# SAMV71_Xplained_Ultra_Power_Converter.net
KiCad netlist of a schematic drawn in Altium Designer
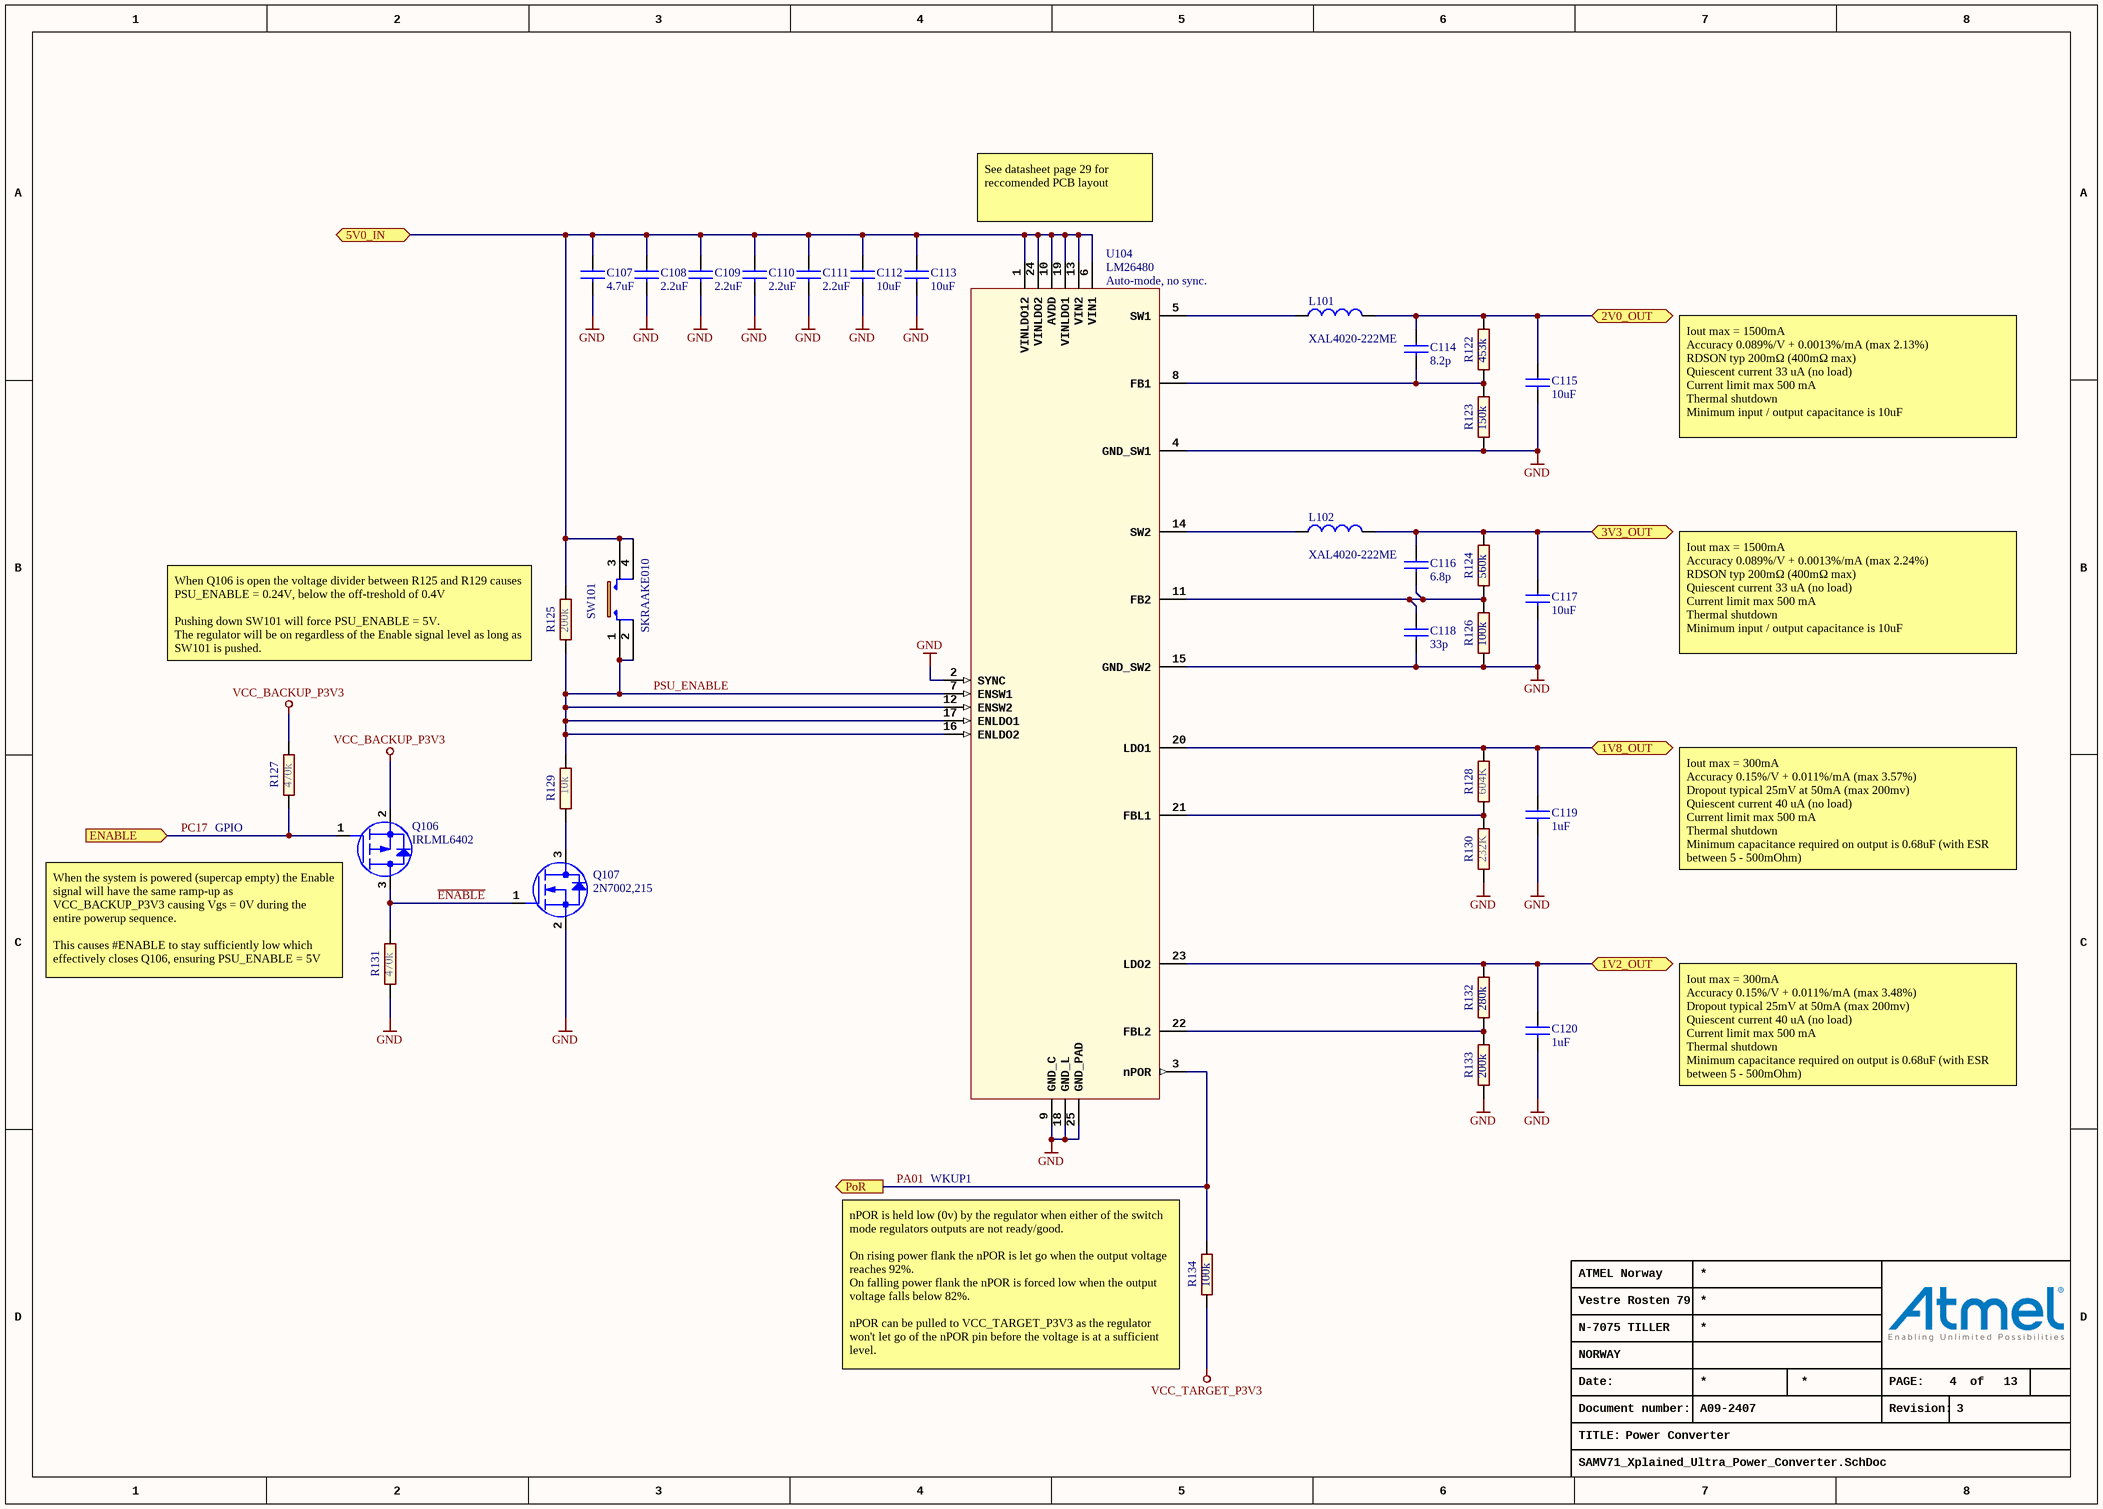
[diagram p0: SAMV71_Xplained_Ultra_Power_Converter.SchDoc]

(export (version "E")
  (design (tool "Eeschema 10.0.6"))
  (components
    (comp (ref "C107")
      (value "4.7uF")
      (footprint "AP1-00039")
      (description "Ceramic capacitor, SMD 0603, X5R, 10V, 10% (de31036)")
      (fields (field (name "TOLERANCE") "10%") (field (name "MANUFACTURER") "tdk"))
      (libsource (lib "AltiumDbLib") (part "CAP-NONPOL"))
    )
    (comp (ref "C108")
      (value "2.2uF")
      (footprint "AP1-00053")
      (description "Ceramic capacitor, SMD 0402, X5R, 6.3V, +/-20%")
      (fields (field (name "TOLERANCE") "Â±20%") (field (name "MANUFACTURER") "Kemet"))
      (libsource (lib "AltiumDbLib") (part "CAP-NONPOL"))
    )
    (comp (ref "C109")
      (value "2.2uF")
      (footprint "AP1-00053")
      (description "Ceramic capacitor, SMD 0402, X5R, 6.3V, +/-20%")
      (fields (field (name "TOLERANCE") "Â±20%") (field (name "MANUFACTURER") "Kemet"))
      (libsource (lib "AltiumDbLib") (part "CAP-NONPOL"))
    )
    (comp (ref "C110")
      (value "2.2uF")
      (footprint "AP1-00053")
      (description "Ceramic capacitor, SMD 0402, X5R, 6.3V, +/-20%")
      (fields (field (name "TOLERANCE") "Â±20%") (field (name "MANUFACTURER") "Kemet"))
      (libsource (lib "AltiumDbLib") (part "CAP-NONPOL"))
    )
    (comp (ref "C111")
      (value "2.2uF")
      (footprint "AP1-00053")
      (description "Ceramic capacitor, SMD 0402, X5R, 6.3V, +/-20%")
      (fields (field (name "TOLERANCE") "Â±20%") (field (name "MANUFACTURER") "Kemet"))
      (libsource (lib "AltiumDbLib") (part "CAP-NONPOL"))
    )
    (comp (ref "C112")
      (value "10uF")
      (footprint "AP1-00041")
      (description "Ceramic capacitor, SMD 0805, X5R, 10V, 10 %, (de19441)")
      (fields (field (name "TOLERANCE") "10%") (field (name "MANUFACTURER") "Murata"))
      (libsource (lib "AltiumDbLib") (part "CAP-NONPOL"))
    )
    (comp (ref "C113")
      (value "10uF")
      (footprint "AP1-00041")
      (description "Ceramic capacitor, SMD 0805, X5R, 10V, 10 %, (de19441)")
      (fields (field (name "TOLERANCE") "10%") (field (name "MANUFACTURER") "Murata"))
      (libsource (lib "AltiumDbLib") (part "CAP-NONPOL"))
    )
    (comp (ref "C114")
      (value "8.2p")
      (footprint "AP1-00053")
      (description "Ceramic capacitor, SMD 0402, NP0, 50V, +/-5%")
      (fields (field (name "TOLERANCE") "50V, +/-5%"))
      (libsource (lib "AltiumDbLib") (part "CAP-NONPOL"))
    )
    (comp (ref "C115")
      (value "10uF")
      (footprint "AP1-00041")
      (description "Ceramic capacitor, SMD 0805, X5R, 10V, 10 %, (de19441)")
      (fields (field (name "TOLERANCE") "10%") (field (name "MANUFACTURER") "Murata"))
      (libsource (lib "AltiumDbLib") (part "CAP-NONPOL"))
    )
    (comp (ref "C116")
      (value "6.8p")
      (footprint "AP1-00053")
      (description "Ceramic capacitor, SMD 0402, NP0, 50V, +/-5%")
      (fields (field (name "TOLERANCE") "50V, +/-5%"))
      (libsource (lib "AltiumDbLib") (part "CAP-NONPOL"))
    )
    (comp (ref "C117")
      (value "10uF")
      (footprint "AP1-00041")
      (description "Ceramic capacitor, SMD 0805, X5R, 10V, 10 %, (de19441)")
      (fields (field (name "TOLERANCE") "10%") (field (name "MANUFACTURER") "Murata"))
      (libsource (lib "AltiumDbLib") (part "CAP-NONPOL"))
    )
    (comp (ref "C118")
      (value "33p")
      (footprint "AP1-00053")
      (description "Ceramic capacitor, SMD 0402, NP0, 50V, +/-5%")
      (fields (field (name "TOLERANCE") "50V, +/-5%"))
      (libsource (lib "AltiumDbLib") (part "CAP-NONPOL"))
    )
    (comp (ref "C119")
      (value "1uF")
      (footprint "AP1-00053")
      (description "Ceramic capacitor, SMD 0402, X5R, 10V, ±10 %")
      (fields (field (name "MANUFACTURER") "AVX") (field (name "MPN") "0402ZD105KAT2A"))
      (libsource (lib "AltiumDbLib") (part "CAP-NONPOL"))
    )
    (comp (ref "C120")
      (value "1uF")
      (footprint "AP1-00053")
      (description "Ceramic capacitor, SMD 0402, X5R, 10V, ±10 %")
      (fields (field (name "MANUFACTURER") "AVX") (field (name "MPN") "0402ZD105KAT2A"))
      (libsource (lib "AltiumDbLib") (part "CAP-NONPOL"))
    )
    (comp (ref "L101")
      (value "XAL4020-222ME")
      (footprint "AP3-00119")
      (description "2.2ÂµH Shielded Power Inductor, 4x4x2mm, Isat=5.6A , Irms=4.0A , DCR=35.2mÎ©")
      (fields (field (name "TOLERANCE") "20%") (field (name "MANUFACTURER") "Coilcraft"))
      (libsource (lib "AltiumDbLib") (part "INDUCTOR"))
    )
    (comp (ref "L102")
      (value "XAL4020-222ME")
      (footprint "AP3-00119")
      (description "2.2ÂµH Shielded Power Inductor, 4x4x2mm, Isat=5.6A , Irms=4.0A , DCR=35.2mÎ©")
      (fields (field (name "TOLERANCE") "20%") (field (name "MANUFACTURER") "Coilcraft"))
      (libsource (lib "AltiumDbLib") (part "INDUCTOR"))
    )
    (comp (ref "Q106")
      (value "IRLML6402")
      (footprint "AP5-00002")
      (description "P-ch. MOSFET. -30V, -3.7A continuous,RDS(ON)=0.05Ohm@VGS=-4,5V, RDS(ON)=0.08Ohm@VGS=-2.5V")
      (fields (field (name "MANUFACTURER") "International Rectifier") (field (name "MPN") "IRLML6402PBF"))
      (libsource (lib "AltiumDbLib") (part "MOSFET_P_GSD"))
    )
    (comp (ref "Q107")
      (value "2N7002,215")
      (footprint "AP5-00002")
      (description "N-Channel MOSFET. 60V, 0.300A continuous, 1.2A Peak. RDS(ON) = 3.8Ohm@VGS=4.5V, VGS(th)<2.5V")
      (fields (field (name "MANUFACTURER") "NXP"))
      (libsource (lib "AltiumDbLib") (part "MOSFET_N_GSD"))
    )
    (comp (ref "R122")
      (value "453k")
      (footprint "AP2-00011")
      (description "Thick film resistor, SMD 0402, 1/16W, 1%")
      (fields (field (name "TOLERANCE") "1 %"))
      (libsource (lib "AltiumDbLib") (part "R2"))
    )
    (comp (ref "R123")
      (value "150k")
      (footprint "AP2-00011")
      (description "Thick film resistor, SMD 0402, 1/16W, 1%")
      (fields (field (name "TOLERANCE") "1 %"))
      (libsource (lib "AltiumDbLib") (part "R2"))
    )
    (comp (ref "R124")
      (value "560k")
      (footprint "AP2-00011")
      (description "Thick film resistor, SMD 0402, 1/16W, 1%")
      (fields (field (name "TOLERANCE") "1 %"))
      (libsource (lib "AltiumDbLib") (part "R2"))
    )
    (comp (ref "R125")
      (value "200k")
      (footprint "AP2-00011")
      (description "Thick film resistor, SMD 0402, 1/16W, 1%")
      (fields (field (name "TOLERANCE") "1 %"))
      (libsource (lib "AltiumDbLib") (part "R2"))
    )
    (comp (ref "R126")
      (value "100k")
      (footprint "AP2-00011")
      (description "Thick film resistor, SMD 0402, 1/16W, 1%")
      (fields (field (name "TOLERANCE") "1 %"))
      (libsource (lib "") (part "R2_1"))
    )
    (comp (ref "R127")
      (value "470k")
      (footprint "AP2-00011")
      (description "Thick film resistor, SMD 0402, 1/16W, 1%")
      (fields (field (name "TOLERANCE") "1 %"))
      (libsource (lib "AltiumDbLib") (part "R2"))
    )
    (comp (ref "R128")
      (value "604K")
      (footprint "AP2-00011")
      (description "Thick film resistor, SMD 0402, 1/16W, 1%")
      (fields (field (name "TOLERANCE") "1 %"))
      (libsource (lib "AltiumDbLib") (part "R2"))
    )
    (comp (ref "R129")
      (value "10k")
      (footprint "AP2-00011")
      (description "Thick film resistor, SMD 0402, 1/16W, 1%")
      (fields (field (name "TOLERANCE") "1 %") (field (name "MANUFACTURER") "vishay"))
      (libsource (lib "AltiumDbLib") (part "R2"))
    )
    (comp (ref "R130")
      (value "232K")
      (footprint "AP2-00011")
      (description "Thick film resistor, SMD 0402, 1/16W, 1%")
      (fields (field (name "TOLERANCE") "1 %"))
      (libsource (lib "AltiumDbLib") (part "R2"))
    )
    (comp (ref "R131")
      (value "470k")
      (footprint "AP2-00011")
      (description "Thick film resistor, SMD 0402, 1/16W, 1%")
      (fields (field (name "TOLERANCE") "1 %"))
      (libsource (lib "AltiumDbLib") (part "R2"))
    )
    (comp (ref "R132")
      (value "280k")
      (footprint "AP2-00011")
      (description "Thick film resistor, SMD 0402, 1/16W, 1%")
      (fields (field (name "TOLERANCE") "1 %"))
      (libsource (lib "AltiumDbLib") (part "R2"))
    )
    (comp (ref "R133")
      (value "200k")
      (footprint "AP2-00011")
      (description "Thick film resistor, SMD 0402, 1/16W, 1%")
      (fields (field (name "TOLERANCE") "1 %"))
      (libsource (lib "AltiumDbLib") (part "R2"))
    )
    (comp (ref "R134")
      (value "100k")
      (footprint "AP2-00011")
      (description "Thick film resistor, SMD 0402, 1/16W, 1%")
      (fields (field (name "TOLERANCE") "1 %"))
      (libsource (lib "") (part "R2_1"))
    )
    (comp (ref "SW101")
      (value "SKRAAKE010")
      (footprint "AP8-00137")
      (description "6.2x6.2 mm SMD tact switch, same as A08-0091 but less force is needed")
      (fields
        (field (name "MANUFACTURER") "ALPS")
        (field (name "Comment") "Can be ordered in low volumes from Mouser")
      )
      (libsource (lib "AltiumDbLib") (part "PUSHBUTTON1"))
    )
    (comp (ref "U104")
      (value "Auto-mode, no sync.")
      (footprint "AP6-00380")
      (description "Externally Programmable Dual High-Current Step-Down DC/DC and Dual Linear Regulators")
      (fields
        (field (name "ALTIUM_VALUE") "LM26480")
        (field (name "MANUFACTURER") "Texas Instruments")
        (field (name "MPN") "LM26480SQ-AA/NOPB")
      )
      (libsource (lib "AltiumDbLib") (part "LM26480"))
    )
  )
  (nets
    (net (code "1") (name "/1V2_OUT") (class "Default")
      (node (ref "C120") (pin "1") (pinfunction "1_1") (pintype "passive"))
      (node (ref "R132") (pin "2") (pinfunction "2_2") (pintype "passive"))
      (node (ref "U104") (pin "23") (pinfunction "LDO2_23") (pintype "power_in"))
    )
    (net (code "2") (name "/1V8_OUT") (class "Default")
      (node (ref "C119") (pin "1") (pinfunction "1_1") (pintype "passive"))
      (node (ref "R128") (pin "2") (pinfunction "2_2") (pintype "passive"))
      (node (ref "U104") (pin "20") (pinfunction "LDO1_20") (pintype "power_in"))
    )
    (net (code "3") (name "/2V0_OUT") (class "Default")
      (node (ref "C114") (pin "1") (pinfunction "1_1") (pintype "passive"))
      (node (ref "C115") (pin "1") (pinfunction "1_1") (pintype "passive"))
      (node (ref "L101") (pin "2") (pinfunction "2_2") (pintype "passive"))
      (node (ref "R122") (pin "2") (pinfunction "2_2") (pintype "passive"))
    )
    (net (code "4") (name "/3V3_OUT") (class "Default")
      (node (ref "C116") (pin "1") (pinfunction "1_1") (pintype "passive"))
      (node (ref "C117") (pin "1") (pinfunction "1_1") (pintype "passive"))
      (node (ref "L102") (pin "2") (pinfunction "2_2") (pintype "passive"))
      (node (ref "R124") (pin "2") (pinfunction "2_2") (pintype "passive"))
    )
    (net (code "5") (name "/5V0_IN") (class "Default")
      (node (ref "C107") (pin "1") (pinfunction "1_1") (pintype "passive"))
      (node (ref "C108") (pin "1") (pinfunction "1_1") (pintype "passive"))
      (node (ref "C109") (pin "1") (pinfunction "1_1") (pintype "passive"))
      (node (ref "C110") (pin "1") (pinfunction "1_1") (pintype "passive"))
      (node (ref "C111") (pin "1") (pinfunction "1_1") (pintype "passive"))
      (node (ref "C112") (pin "1") (pinfunction "1_1") (pintype "passive"))
      (node (ref "C113") (pin "1") (pinfunction "1_1") (pintype "passive"))
      (node (ref "R125") (pin "2") (pinfunction "2_2") (pintype "passive"))
      (node (ref "SW101") (pin "3") (pinfunction "3_3") (pintype "passive"))
      (node (ref "SW101") (pin "4") (pinfunction "4_4") (pintype "passive"))
      (node (ref "U104") (pin "1") (pinfunction "VINLDO12_1") (pintype "power_in"))
      (node (ref "U104") (pin "10") (pinfunction "AVDD_10") (pintype "power_in"))
      (node (ref "U104") (pin "13") (pinfunction "VIN2_13") (pintype "power_in"))
      (node (ref "U104") (pin "19") (pinfunction "VINLDO1_19") (pintype "power_in"))
      (node (ref "U104") (pin "24") (pinfunction "VINLDO2_24") (pintype "power_in"))
      (node (ref "U104") (pin "6") (pinfunction "VIN1_6") (pintype "power_in"))
    )
    (net (code "6") (name "/PA01") (class "Default")
      (node (ref "R134") (pin "1") (pinfunction "1_1") (pintype "passive"))
      (node (ref "U104") (pin "3") (pinfunction "nPOR_3") (pintype "output"))
    )
    (net (code "7") (name "/PC17") (class "Default")
      (node (ref "Q106") (pin "1") (pinfunction "G_1") (pintype "passive"))
      (node (ref "R127") (pin "1") (pinfunction "1_1") (pintype "passive"))
    )
    (net (code "8") (name "/PSU_ENABLE") (class "Default")
      (node (ref "R125") (pin "1") (pinfunction "1_1") (pintype "passive"))
      (node (ref "R129") (pin "2") (pinfunction "2_2") (pintype "passive"))
      (node (ref "SW101") (pin "1") (pinfunction "1_1") (pintype "passive"))
      (node (ref "SW101") (pin "2") (pinfunction "2_2") (pintype "passive"))
      (node (ref "U104") (pin "12") (pinfunction "ENSW2_12") (pintype "input"))
      (node (ref "U104") (pin "16") (pinfunction "ENLDO2_16") (pintype "input"))
      (node (ref "U104") (pin "17") (pinfunction "ENLDO1_17") (pintype "input"))
      (node (ref "U104") (pin "7") (pinfunction "ENSW1_7") (pintype "input"))
    )
    (net (code "9") (name "/~{ENABLE}") (class "Default")
      (node (ref "Q106") (pin "3") (pinfunction "D_3") (pintype "passive"))
      (node (ref "Q107") (pin "1") (pinfunction "G_1") (pintype "passive"))
      (node (ref "R131") (pin "2") (pinfunction "2_2") (pintype "passive"))
    )
    (net (code "10") (name "GND") (class "Default")
      (node (ref "C107") (pin "2") (pinfunction "2_2") (pintype "passive"))
      (node (ref "C108") (pin "2") (pinfunction "2_2") (pintype "passive"))
      (node (ref "C109") (pin "2") (pinfunction "2_2") (pintype "passive"))
      (node (ref "C110") (pin "2") (pinfunction "2_2") (pintype "passive"))
      (node (ref "C111") (pin "2") (pinfunction "2_2") (pintype "passive"))
      (node (ref "C112") (pin "2") (pinfunction "2_2") (pintype "passive"))
      (node (ref "C113") (pin "2") (pinfunction "2_2") (pintype "passive"))
      (node (ref "C115") (pin "2") (pinfunction "2_2") (pintype "passive"))
      (node (ref "C117") (pin "2") (pinfunction "2_2") (pintype "passive"))
      (node (ref "C118") (pin "2") (pinfunction "2_2") (pintype "passive"))
      (node (ref "C119") (pin "2") (pinfunction "2_2") (pintype "passive"))
      (node (ref "C120") (pin "2") (pinfunction "2_2") (pintype "passive"))
      (node (ref "Q107") (pin "2") (pinfunction "S_2") (pintype "passive"))
      (node (ref "R123") (pin "1") (pinfunction "1_1") (pintype "passive"))
      (node (ref "R126") (pin "2") (pinfunction "2_2") (pintype "passive"))
      (node (ref "R130") (pin "1") (pinfunction "1_1") (pintype "passive"))
      (node (ref "R131") (pin "1") (pinfunction "1_1") (pintype "passive"))
      (node (ref "R133") (pin "1") (pinfunction "1_1") (pintype "passive"))
      (node (ref "U104") (pin "15") (pinfunction "GND_SW2_15") (pintype "power_in"))
      (node (ref "U104") (pin "18") (pinfunction "GND_L_18") (pintype "power_in"))
      (node (ref "U104") (pin "2") (pinfunction "SYNC_2") (pintype "input"))
      (node (ref "U104") (pin "25") (pinfunction "GND_PAD_25") (pintype "passive"))
      (node (ref "U104") (pin "4") (pinfunction "GND_SW1_4") (pintype "power_in"))
      (node (ref "U104") (pin "9") (pinfunction "GND_C_9") (pintype "power_in"))
    )
    (net (code "11") (name "Net-(Q107-D)") (class "Default")
      (node (ref "Q107") (pin "3") (pinfunction "D_3") (pintype "passive"))
      (node (ref "R129") (pin "1") (pinfunction "1_1") (pintype "passive"))
    )
    (net (code "12") (name "Net-(U104-FB1)") (class "Default")
      (node (ref "C114") (pin "2") (pinfunction "2_2") (pintype "passive"))
      (node (ref "R122") (pin "1") (pinfunction "1_1") (pintype "passive"))
      (node (ref "R123") (pin "2") (pinfunction "2_2") (pintype "passive"))
      (node (ref "U104") (pin "8") (pinfunction "FB1_8") (pintype "power_in"))
    )
    (net (code "13") (name "Net-(U104-FB2)") (class "Default")
      (node (ref "C116") (pin "2") (pinfunction "2_2") (pintype "passive"))
      (node (ref "C118") (pin "1") (pinfunction "1_1") (pintype "passive"))
      (node (ref "R124") (pin "1") (pinfunction "1_1") (pintype "passive"))
      (node (ref "R126") (pin "1") (pinfunction "1_1") (pintype "passive"))
      (node (ref "U104") (pin "11") (pinfunction "FB2_11") (pintype "power_in"))
    )
    (net (code "14") (name "Net-(U104-FBL1)") (class "Default")
      (node (ref "R128") (pin "1") (pinfunction "1_1") (pintype "passive"))
      (node (ref "R130") (pin "2") (pinfunction "2_2") (pintype "passive"))
      (node (ref "U104") (pin "21") (pinfunction "FBL1_21") (pintype "power_in"))
    )
    (net (code "15") (name "Net-(U104-FBL2)") (class "Default")
      (node (ref "R132") (pin "1") (pinfunction "1_1") (pintype "passive"))
      (node (ref "R133") (pin "2") (pinfunction "2_2") (pintype "passive"))
      (node (ref "U104") (pin "22") (pinfunction "FBL2_22") (pintype "power_in"))
    )
    (net (code "16") (name "Net-(U104-SW1)") (class "Default")
      (node (ref "L101") (pin "1") (pinfunction "1_1") (pintype "passive"))
      (node (ref "U104") (pin "5") (pinfunction "SW1_5") (pintype "power_in"))
    )
    (net (code "17") (name "Net-(U104-SW2)") (class "Default")
      (node (ref "L102") (pin "1") (pinfunction "1_1") (pintype "passive"))
      (node (ref "U104") (pin "14") (pinfunction "SW2_14") (pintype "power_in"))
    )
    (net (code "18") (name "VCC_BACKUP_P3V3") (class "Default")
      (node (ref "Q106") (pin "2") (pinfunction "S_2") (pintype "passive"))
      (node (ref "R127") (pin "2") (pinfunction "2_2") (pintype "passive"))
    )
    (net (code "19") (name "VCC_TARGET_P3V3") (class "Default")
      (node (ref "R134") (pin "2") (pinfunction "2_2") (pintype "passive"))
    )
  )
)
